# PART_2.net
KiCad netlist of a schematic drawn in Altium Designer
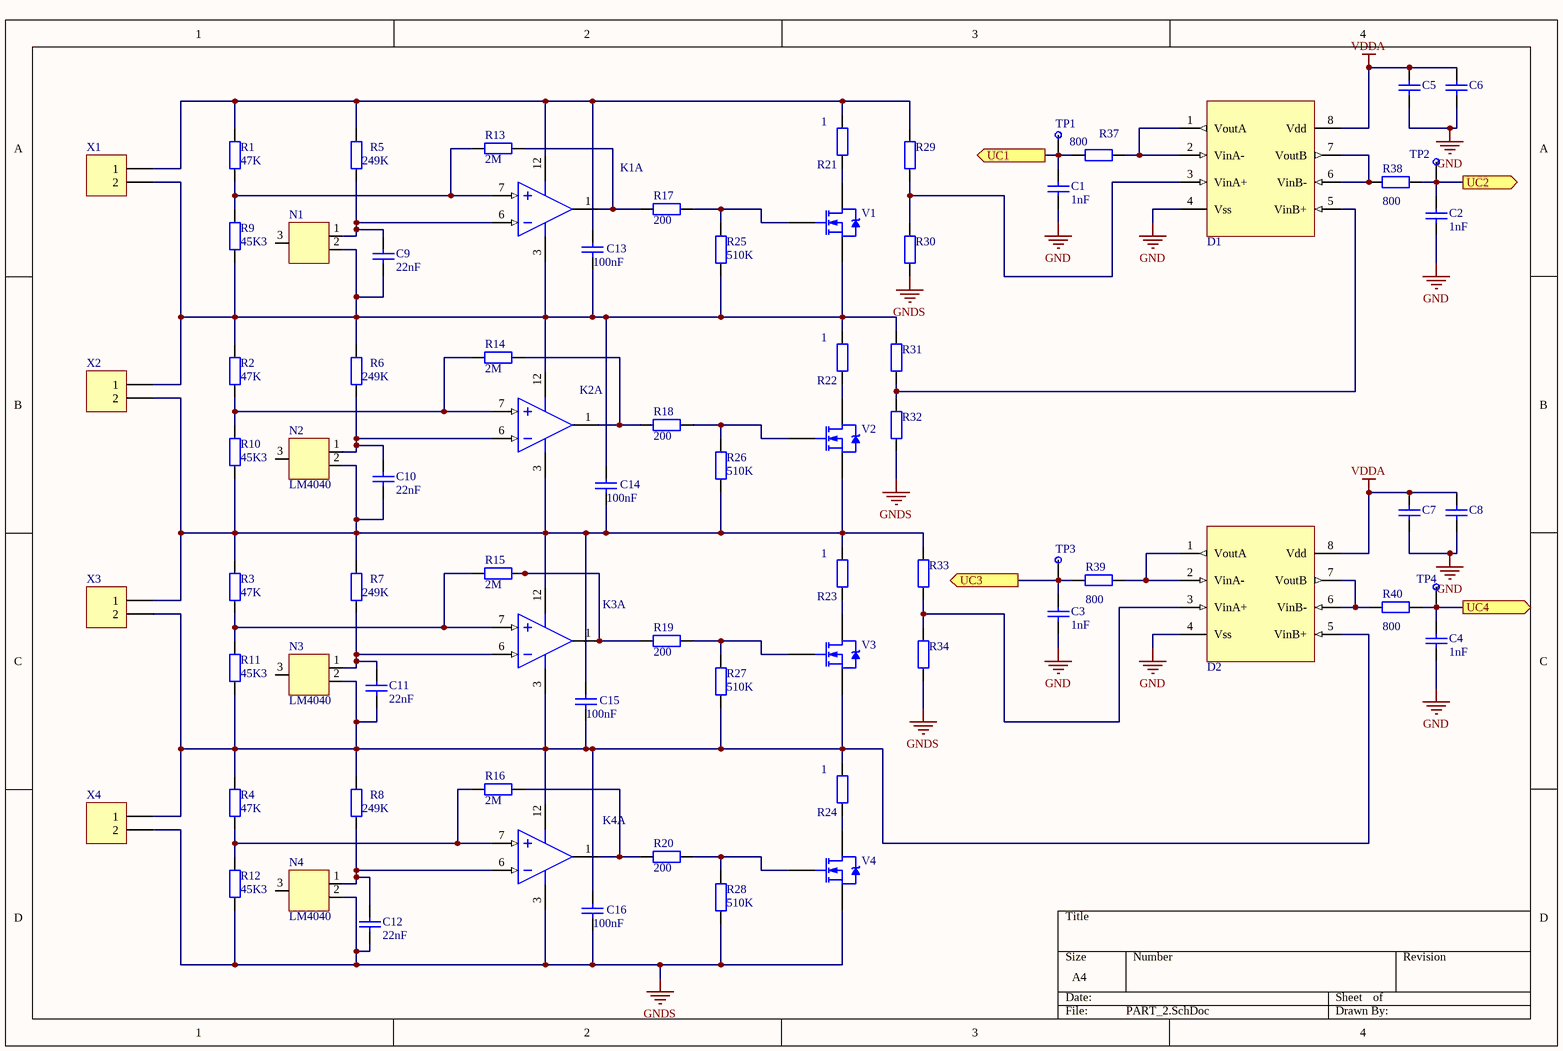
[diagram p0: PART_2.SchDoc]

(export (version "E")
  (design (tool "Eeschema 10.0.6"))
  (components
    (comp (ref "C1")
      (value "1nF")
      (footprint "C0805")
      (description "Capacitor")
      (fields (field (name "Comment") "Cap"))
      (libsource (lib "Miscellaneous Devices") (part "Cap"))
    )
    (comp (ref "C2")
      (value "1nF")
      (footprint "C0805")
      (description "Capacitor")
      (fields (field (name "Comment") "Cap"))
      (libsource (lib "Miscellaneous Devices") (part "Cap"))
    )
    (comp (ref "C3")
      (value "1nF")
      (footprint "C0805")
      (description "Capacitor")
      (fields (field (name "Comment") "Cap"))
      (libsource (lib "Miscellaneous Devices") (part "Cap"))
    )
    (comp (ref "C4")
      (value "1nF")
      (footprint "C0805")
      (description "Capacitor")
      (fields (field (name "Comment") "Cap"))
      (libsource (lib "Miscellaneous Devices") (part "Cap"))
    )
    (comp (ref "C5")
      (value "Cap")
      (footprint "C0805")
      (description "Capacitor")
      (libsource (lib "Miscellaneous Devices") (part "Cap"))
    )
    (comp (ref "C6")
      (value "Cap")
      (footprint "C0805")
      (description "Capacitor")
      (libsource (lib "Miscellaneous Devices") (part "Cap"))
    )
    (comp (ref "C7")
      (value "Cap")
      (footprint "C0805")
      (description "Capacitor")
      (libsource (lib "Miscellaneous Devices") (part "Cap"))
    )
    (comp (ref "C8")
      (value "Cap")
      (footprint "C0805")
      (description "Capacitor")
      (libsource (lib "Miscellaneous Devices") (part "Cap"))
    )
    (comp (ref "C9")
      (value "22nF")
      (footprint "C0805")
      (description "Capacitor")
      (fields (field (name "Comment") "Cap"))
      (libsource (lib "Miscellaneous Devices") (part "Cap"))
    )
    (comp (ref "C10")
      (value "22nF")
      (footprint "C0805")
      (description "Capacitor")
      (fields (field (name "Comment") "Cap"))
      (libsource (lib "Miscellaneous Devices") (part "Cap"))
    )
    (comp (ref "C11")
      (value "22nF")
      (footprint "C0805")
      (description "Capacitor")
      (fields (field (name "Comment") "Cap"))
      (libsource (lib "Miscellaneous Devices") (part "Cap"))
    )
    (comp (ref "C12")
      (value "22nF")
      (footprint "C0805")
      (description "Capacitor")
      (fields (field (name "Comment") "Cap"))
      (libsource (lib "Miscellaneous Devices") (part "Cap"))
    )
    (comp (ref "C13")
      (value "100nF")
      (footprint "C0805")
      (description "Capacitor")
      (fields (field (name "Comment") "Cap"))
      (libsource (lib "Miscellaneous Devices") (part "Cap"))
    )
    (comp (ref "C14")
      (value "100nF")
      (footprint "C0805")
      (description "Capacitor")
      (fields (field (name "Comment") "Cap"))
      (libsource (lib "Miscellaneous Devices") (part "Cap"))
    )
    (comp (ref "C15")
      (value "100nF")
      (footprint "C0805")
      (description "Capacitor")
      (fields (field (name "Comment") "Cap"))
      (libsource (lib "Miscellaneous Devices") (part "Cap"))
    )
    (comp (ref "C16")
      (value "100nF")
      (footprint "C0805")
      (description "Capacitor")
      (fields (field (name "Comment") "Cap"))
      (libsource (lib "Miscellaneous Devices") (part "Cap"))
    )
    (comp (ref "D1")
      (value "~")
      (footprint "MSOP za op.pojacalo")
      (libsource (lib "komponente") (part "Amplifier"))
    )
    (comp (ref "D2")
      (value "~")
      (footprint "MSOP za op.pojacalo")
      (libsource (lib "komponente") (part "Amplifier"))
    )
    (comp (ref "K1")
      (value "TLC3704QJ")
      (footprint "TSSOP5-3")
      (description "Low Power Quad Differential Comparator")
      (libsource (lib "TI Analog Comparator") (part "LP2901D"))
    )
    (comp (ref "K2")
      (value "TLC3704QJ")
      (footprint "TSSOP5-3")
      (description "Low Power Quad Differential Comparator")
      (libsource (lib "TI Analog Comparator") (part "LP2901D"))
    )
    (comp (ref "K3")
      (value "TLC3704QJ")
      (footprint "TSSOP5-3")
      (description "Low Power Quad Differential Comparator")
      (libsource (lib "TI Analog Comparator") (part "LP2901D"))
    )
    (comp (ref "K4")
      (value "TLC3704QJ")
      (footprint "TSSOP5-3")
      (description "Low Power Quad Differential Comparator")
      (libsource (lib "TI Analog Comparator") (part "LP2901D"))
    )
    (comp (ref "N1")
      (value "~")
      (footprint "SOT-23-ref_chip")
      (libsource (lib "komponente") (part "referentni chip"))
    )
    (comp (ref "N2")
      (value "LM4040")
      (footprint "SOT-23-ref_chip")
      (libsource (lib "komponente") (part "referentni chip"))
    )
    (comp (ref "N3")
      (value "LM4040")
      (footprint "SOT-23-ref_chip")
      (libsource (lib "komponente") (part "referentni chip"))
    )
    (comp (ref "N4")
      (value "LM4040")
      (footprint "SOT-23-ref_chip")
      (libsource (lib "komponente") (part "referentni chip"))
    )
    (comp (ref "R1")
      (value "47K")
      (footprint "C0805")
      (description "Resistor")
      (libsource (lib "Miscellaneous Devices") (part "Res2"))
    )
    (comp (ref "R2")
      (value "47K")
      (footprint "C0805")
      (description "Resistor")
      (libsource (lib "Miscellaneous Devices") (part "Res2"))
    )
    (comp (ref "R3")
      (value "47K")
      (footprint "C0805")
      (description "Resistor")
      (libsource (lib "Miscellaneous Devices") (part "Res2"))
    )
    (comp (ref "R4")
      (value "47K")
      (footprint "C0805")
      (description "Resistor")
      (libsource (lib "Miscellaneous Devices") (part "Res2"))
    )
    (comp (ref "R5")
      (value "249K")
      (footprint "C0805")
      (description "Resistor")
      (libsource (lib "Miscellaneous Devices") (part "Res2"))
    )
    (comp (ref "R6")
      (value "249K")
      (footprint "C0805")
      (description "Resistor")
      (libsource (lib "Miscellaneous Devices") (part "Res2"))
    )
    (comp (ref "R7")
      (value "249K")
      (footprint "C0805")
      (description "Resistor")
      (libsource (lib "Miscellaneous Devices") (part "Res2"))
    )
    (comp (ref "R8")
      (value "249K")
      (footprint "C0805")
      (description "Resistor")
      (libsource (lib "Miscellaneous Devices") (part "Res2"))
    )
    (comp (ref "R9")
      (value "45K3")
      (footprint "C0805")
      (description "Resistor")
      (libsource (lib "Miscellaneous Devices") (part "Res2"))
    )
    (comp (ref "R10")
      (value "45K3")
      (footprint "C0805")
      (description "Resistor")
      (libsource (lib "Miscellaneous Devices") (part "Res2"))
    )
    (comp (ref "R11")
      (value "45K3")
      (footprint "C0805")
      (description "Resistor")
      (libsource (lib "Miscellaneous Devices") (part "Res2"))
    )
    (comp (ref "R12")
      (value "45K3")
      (footprint "C0805")
      (description "Resistor")
      (libsource (lib "Miscellaneous Devices") (part "Res2"))
    )
    (comp (ref "R13")
      (value "2M")
      (footprint "C0805")
      (description "Resistor")
      (libsource (lib "") (part "Res2_1"))
    )
    (comp (ref "R14")
      (value "2M")
      (footprint "C0805")
      (description "Resistor")
      (libsource (lib "") (part "Res2_1"))
    )
    (comp (ref "R15")
      (value "2M")
      (footprint "C0805")
      (description "Resistor")
      (libsource (lib "") (part "Res2_1"))
    )
    (comp (ref "R16")
      (value "2M")
      (footprint "C0805")
      (description "Resistor")
      (libsource (lib "") (part "Res2_1"))
    )
    (comp (ref "R17")
      (value "200")
      (footprint "C0805")
      (description "Resistor")
      (libsource (lib "") (part "Res2_1"))
    )
    (comp (ref "R18")
      (value "200")
      (footprint "C0805")
      (description "Resistor")
      (libsource (lib "") (part "Res2_1"))
    )
    (comp (ref "R19")
      (value "200")
      (footprint "C0805")
      (description "Resistor")
      (libsource (lib "") (part "Res2_1"))
    )
    (comp (ref "R20")
      (value "200")
      (footprint "C0805")
      (description "Resistor")
      (libsource (lib "") (part "Res2_1"))
    )
    (comp (ref "R21")
      (value "1")
      (footprint "F za 7W otpornik")
      (description "Resistor")
      (libsource (lib "Miscellaneous Devices") (part "Res2"))
    )
    (comp (ref "R22")
      (value "1")
      (footprint "F za 7W otpornik")
      (description "Resistor")
      (libsource (lib "Miscellaneous Devices") (part "Res2"))
    )
    (comp (ref "R23")
      (value "1")
      (footprint "F za 7W otpornik")
      (description "Resistor")
      (libsource (lib "Miscellaneous Devices") (part "Res2"))
    )
    (comp (ref "R24")
      (value "1")
      (footprint "F za 7W otpornik")
      (description "Resistor")
      (libsource (lib "Miscellaneous Devices") (part "Res2"))
    )
    (comp (ref "R25")
      (value "510K")
      (footprint "C0805")
      (description "Resistor")
      (libsource (lib "Miscellaneous Devices") (part "Res2"))
    )
    (comp (ref "R26")
      (value "510K")
      (footprint "C0805")
      (description "Resistor")
      (libsource (lib "Miscellaneous Devices") (part "Res2"))
    )
    (comp (ref "R27")
      (value "510K")
      (footprint "C0805")
      (description "Resistor")
      (libsource (lib "Miscellaneous Devices") (part "Res2"))
    )
    (comp (ref "R28")
      (value "510K")
      (footprint "C0805")
      (description "Resistor")
      (libsource (lib "Miscellaneous Devices") (part "Res2"))
    )
    (comp (ref "R29")
      (value "~")
      (footprint "C0805")
      (description "Resistor")
      (libsource (lib "Miscellaneous Devices") (part "Res2"))
    )
    (comp (ref "R30")
      (value "~")
      (footprint "C0805")
      (description "Resistor")
      (libsource (lib "Miscellaneous Devices") (part "Res2"))
    )
    (comp (ref "R31")
      (value "~")
      (footprint "C0805")
      (description "Resistor")
      (libsource (lib "Miscellaneous Devices") (part "Res2"))
    )
    (comp (ref "R32")
      (value "~")
      (footprint "C0805")
      (description "Resistor")
      (libsource (lib "Miscellaneous Devices") (part "Res2"))
    )
    (comp (ref "R33")
      (value "~")
      (footprint "C0805")
      (description "Resistor")
      (libsource (lib "Miscellaneous Devices") (part "Res2"))
    )
    (comp (ref "R34")
      (value "~")
      (footprint "C0805")
      (description "Resistor")
      (libsource (lib "Miscellaneous Devices") (part "Res2"))
    )
    (comp (ref "R37")
      (value "800")
      (footprint "C0805")
      (description "Resistor")
      (libsource (lib "") (part "Res2_1"))
    )
    (comp (ref "R38")
      (value "800")
      (footprint "C0805")
      (description "Resistor")
      (libsource (lib "") (part "Res2_2"))
    )
    (comp (ref "R39")
      (value "800")
      (footprint "C0805")
      (description "Resistor")
      (libsource (lib "") (part "Res2_2"))
    )
    (comp (ref "R40")
      (value "800")
      (footprint "C0805")
      (description "Resistor")
      (libsource (lib "") (part "Res2_2"))
    )
    (comp (ref "TP1")
      (value "testpoint")
      (footprint "Test_point")
      (libsource (lib "komponente") (part "testpoint"))
    )
    (comp (ref "TP2")
      (value "testpoint")
      (footprint "Test_point")
      (libsource (lib "komponente") (part "testpoint"))
    )
    (comp (ref "TP3")
      (value "testpoint")
      (footprint "Test_point")
      (libsource (lib "komponente") (part "testpoint"))
    )
    (comp (ref "TP4")
      (value "testpoint")
      (footprint "Test_point")
      (libsource (lib "komponente") (part "testpoint"))
    )
    (comp (ref "V1")
      (value "NMOS-2")
      (footprint "sot23_transistors")
      (description "N-Channel Power MOSFET")
      (libsource (lib "Miscellaneous Devices") (part "NMOS-2"))
    )
    (comp (ref "V2")
      (value "NMOS-2")
      (footprint "sot23_transistors")
      (description "N-Channel Power MOSFET")
      (libsource (lib "Miscellaneous Devices") (part "NMOS-2"))
    )
    (comp (ref "V3")
      (value "NMOS-2")
      (footprint "sot23_transistors")
      (description "N-Channel Power MOSFET")
      (libsource (lib "Miscellaneous Devices") (part "NMOS-2"))
    )
    (comp (ref "V4")
      (value "NMOS-2")
      (footprint "sot23_transistors")
      (description "N-Channel Power MOSFET")
      (libsource (lib "Miscellaneous Devices") (part "NMOS-2"))
    )
    (comp (ref "X1")
      (value "Header 2")
      (footprint "F Header 1x2")
      (description "Header, 2-Pin")
      (libsource (lib "Miscellaneous Connectors") (part "Header 2"))
    )
    (comp (ref "X2")
      (value "Header 2")
      (footprint "F Header 1x2")
      (description "Header, 2-Pin")
      (libsource (lib "Miscellaneous Connectors") (part "Header 2"))
    )
    (comp (ref "X3")
      (value "Header 2")
      (footprint "F Header 1x2")
      (description "Header, 2-Pin")
      (libsource (lib "Miscellaneous Connectors") (part "Header 2"))
    )
    (comp (ref "X4")
      (value "Header 2")
      (footprint "F Header 1x2")
      (description "Header, 2-Pin")
      (libsource (lib "Miscellaneous Connectors") (part "Header 2"))
    )
  )
  (nets
    (net (code "1") (name "/UC1") (class "Default")
      (node (ref "C1") (pin "2") (pinfunction "2_2") (pintype "passive"))
      (node (ref "R37") (pin "2") (pinfunction "2_2") (pintype "passive"))
      (node (ref "TP1") (pin "1") (pinfunction "1_1") (pintype "passive"))
    )
    (net (code "2") (name "/UC2") (class "Default")
      (node (ref "C2") (pin "2") (pinfunction "2_2") (pintype "passive"))
      (node (ref "R38") (pin "2") (pinfunction "2_2") (pintype "passive"))
      (node (ref "TP2") (pin "1") (pinfunction "1_1") (pintype "passive"))
    )
    (net (code "3") (name "/UC3") (class "Default")
      (node (ref "C3") (pin "2") (pinfunction "2_2") (pintype "passive"))
      (node (ref "R39") (pin "1") (pinfunction "1_1") (pintype "passive"))
      (node (ref "TP3") (pin "1") (pinfunction "1_1") (pintype "passive"))
    )
    (net (code "4") (name "/UC4") (class "Default")
      (node (ref "C4") (pin "2") (pinfunction "2_2") (pintype "passive"))
      (node (ref "R40") (pin "2") (pinfunction "2_2") (pintype "passive"))
      (node (ref "TP4") (pin "1") (pinfunction "1_1") (pintype "passive"))
    )
    (net (code "5") (name "GND") (class "Default")
      (node (ref "C1") (pin "1") (pinfunction "1_1") (pintype "passive"))
      (node (ref "C2") (pin "1") (pinfunction "1_1") (pintype "passive"))
      (node (ref "C3") (pin "1") (pinfunction "1_1") (pintype "passive"))
      (node (ref "C4") (pin "1") (pinfunction "1_1") (pintype "passive"))
      (node (ref "C5") (pin "1") (pinfunction "1_1") (pintype "passive"))
      (node (ref "C6") (pin "1") (pinfunction "1_1") (pintype "passive"))
      (node (ref "C7") (pin "1") (pinfunction "1_1") (pintype "passive"))
      (node (ref "C8") (pin "1") (pinfunction "1_1") (pintype "passive"))
      (node (ref "D1") (pin "4") (pinfunction "Vss_4") (pintype "power_in"))
      (node (ref "D2") (pin "4") (pinfunction "Vss_4") (pintype "power_in"))
    )
    (net (code "6") (name "GNDS") (class "Default")
      (node (ref "C12") (pin "1") (pinfunction "1_1") (pintype "passive"))
      (node (ref "C16") (pin "2") (pinfunction "2_2") (pintype "passive"))
      (node (ref "K4") (pin "3") (pinfunction "V+_3") (pintype "passive"))
      (node (ref "N4") (pin "2") (pinfunction "2_2") (pintype "passive"))
      (node (ref "R12") (pin "1") (pinfunction "1_1") (pintype "passive"))
      (node (ref "R28") (pin "1") (pinfunction "1_1") (pintype "passive"))
      (node (ref "R30") (pin "1") (pinfunction "1_1") (pintype "passive"))
      (node (ref "R32") (pin "1") (pinfunction "1_1") (pintype "passive"))
      (node (ref "R34") (pin "1") (pinfunction "1_1") (pintype "passive"))
      (node (ref "V4") (pin "3") (pinfunction "S_3") (pintype "passive"))
      (node (ref "X4") (pin "2") (pinfunction "2_2") (pintype "passive"))
    )
    (net (code "7") (name "Net-(D1-VinA+)") (class "Default")
      (node (ref "D1") (pin "3") (pinfunction "VinA+_3") (pintype "input"))
      (node (ref "R29") (pin "1") (pinfunction "1_1") (pintype "passive"))
      (node (ref "R30") (pin "2") (pinfunction "2_2") (pintype "passive"))
    )
    (net (code "8") (name "Net-(D1-VinA-)") (class "Default")
      (node (ref "D1") (pin "1") (pinfunction "VoutA_1") (pintype "output"))
      (node (ref "D1") (pin "2") (pinfunction "VinA-_2") (pintype "input"))
      (node (ref "R37") (pin "1") (pinfunction "1_1") (pintype "passive"))
    )
    (net (code "9") (name "Net-(D1-VinB+)") (class "Default")
      (node (ref "D1") (pin "5") (pinfunction "VinB+_5") (pintype "input"))
      (node (ref "R31") (pin "1") (pinfunction "1_1") (pintype "passive"))
      (node (ref "R32") (pin "2") (pinfunction "2_2") (pintype "passive"))
    )
    (net (code "10") (name "Net-(D1-VinB-)") (class "Default")
      (node (ref "D1") (pin "6") (pinfunction "VinB-_6") (pintype "input"))
      (node (ref "D1") (pin "7") (pinfunction "VoutB_7") (pintype "output"))
      (node (ref "R38") (pin "1") (pinfunction "1_1") (pintype "passive"))
    )
    (net (code "11") (name "Net-(D2-VinA+)") (class "Default")
      (node (ref "D2") (pin "3") (pinfunction "VinA+_3") (pintype "input"))
      (node (ref "R33") (pin "1") (pinfunction "1_1") (pintype "passive"))
      (node (ref "R34") (pin "2") (pinfunction "2_2") (pintype "passive"))
    )
    (net (code "12") (name "Net-(D2-VinA-)") (class "Default")
      (node (ref "D2") (pin "1") (pinfunction "VoutA_1") (pintype "output"))
      (node (ref "D2") (pin "2") (pinfunction "VinA-_2") (pintype "input"))
      (node (ref "R39") (pin "2") (pinfunction "2_2") (pintype "passive"))
    )
    (net (code "13") (name "Net-(D2-VinB+)") (class "Default")
      (node (ref "C11") (pin "1") (pinfunction "1_1") (pintype "passive"))
      (node (ref "C15") (pin "2") (pinfunction "2_2") (pintype "passive"))
      (node (ref "C16") (pin "1") (pinfunction "1_1") (pintype "passive"))
      (node (ref "D2") (pin "5") (pinfunction "VinB+_5") (pintype "input"))
      (node (ref "K3") (pin "3") (pinfunction "V+_3") (pintype "passive"))
      (node (ref "K4") (pin "12") (pinfunction "V-_12") (pintype "passive"))
      (node (ref "N3") (pin "2") (pinfunction "2_2") (pintype "passive"))
      (node (ref "R11") (pin "1") (pinfunction "1_1") (pintype "passive"))
      (node (ref "R24") (pin "2") (pinfunction "2_2") (pintype "passive"))
      (node (ref "R27") (pin "1") (pinfunction "1_1") (pintype "passive"))
      (node (ref "R4") (pin "2") (pinfunction "2_2") (pintype "passive"))
      (node (ref "R8") (pin "2") (pinfunction "2_2") (pintype "passive"))
      (node (ref "V3") (pin "3") (pinfunction "S_3") (pintype "passive"))
      (node (ref "X3") (pin "2") (pinfunction "2_2") (pintype "passive"))
      (node (ref "X4") (pin "1") (pinfunction "1_1") (pintype "passive"))
    )
    (net (code "14") (name "Net-(D2-VinB-)") (class "Default")
      (node (ref "D2") (pin "6") (pinfunction "VinB-_6") (pintype "input"))
      (node (ref "D2") (pin "7") (pinfunction "VoutB_7") (pintype "output"))
      (node (ref "R40") (pin "1") (pinfunction "1_1") (pintype "passive"))
    )
    (net (code "15") (name "Net-(K1A-IN+)") (class "Default")
      (node (ref "K1") (pin "7") (pinfunction "IN+_7") (pintype "input"))
      (node (ref "R1") (pin "1") (pinfunction "1_1") (pintype "passive"))
      (node (ref "R13") (pin "2") (pinfunction "2_2") (pintype "passive"))
      (node (ref "R9") (pin "2") (pinfunction "2_2") (pintype "passive"))
    )
    (net (code "16") (name "Net-(K1A-IN-)") (class "Default")
      (node (ref "C9") (pin "2") (pinfunction "2_2") (pintype "passive"))
      (node (ref "K1") (pin "6") (pinfunction "IN-_6") (pintype "input"))
      (node (ref "N1") (pin "1") (pinfunction "1_1") (pintype "bidirectional"))
      (node (ref "R5") (pin "1") (pinfunction "1_1") (pintype "passive"))
    )
    (net (code "17") (name "Net-(K1A-OUT)") (class "Default")
      (node (ref "K1") (pin "1") (pinfunction "OUT_1") (pintype "open_collector"))
      (node (ref "R13") (pin "1") (pinfunction "1_1") (pintype "passive"))
      (node (ref "R17") (pin "2") (pinfunction "2_2") (pintype "passive"))
    )
    (net (code "18") (name "Net-(K1A-V+)") (class "Default")
      (node (ref "C13") (pin "2") (pinfunction "2_2") (pintype "passive"))
      (node (ref "C14") (pin "1") (pinfunction "1_1") (pintype "passive"))
      (node (ref "C9") (pin "1") (pinfunction "1_1") (pintype "passive"))
      (node (ref "K1") (pin "3") (pinfunction "V+_3") (pintype "passive"))
      (node (ref "K2") (pin "12") (pinfunction "V-_12") (pintype "passive"))
      (node (ref "N1") (pin "2") (pinfunction "2_2") (pintype "passive"))
      (node (ref "R2") (pin "2") (pinfunction "2_2") (pintype "passive"))
      (node (ref "R22") (pin "2") (pinfunction "2_2") (pintype "passive"))
      (node (ref "R25") (pin "1") (pinfunction "1_1") (pintype "passive"))
      (node (ref "R31") (pin "2") (pinfunction "2_2") (pintype "passive"))
      (node (ref "R6") (pin "2") (pinfunction "2_2") (pintype "passive"))
      (node (ref "R9") (pin "1") (pinfunction "1_1") (pintype "passive"))
      (node (ref "V1") (pin "3") (pinfunction "S_3") (pintype "passive"))
      (node (ref "X1") (pin "2") (pinfunction "2_2") (pintype "passive"))
      (node (ref "X2") (pin "1") (pinfunction "1_1") (pintype "passive"))
    )
    (net (code "19") (name "Net-(K1A-V-)") (class "Default")
      (node (ref "C13") (pin "1") (pinfunction "1_1") (pintype "passive"))
      (node (ref "K1") (pin "12") (pinfunction "V-_12") (pintype "passive"))
      (node (ref "R1") (pin "2") (pinfunction "2_2") (pintype "passive"))
      (node (ref "R21") (pin "2") (pinfunction "2_2") (pintype "passive"))
      (node (ref "R29") (pin "2") (pinfunction "2_2") (pintype "passive"))
      (node (ref "R5") (pin "2") (pinfunction "2_2") (pintype "passive"))
      (node (ref "X1") (pin "1") (pinfunction "1_1") (pintype "passive"))
    )
    (net (code "20") (name "Net-(K2A-IN+)") (class "Default")
      (node (ref "K2") (pin "7") (pinfunction "IN+_7") (pintype "input"))
      (node (ref "R10") (pin "2") (pinfunction "2_2") (pintype "passive"))
      (node (ref "R14") (pin "2") (pinfunction "2_2") (pintype "passive"))
      (node (ref "R2") (pin "1") (pinfunction "1_1") (pintype "passive"))
    )
    (net (code "21") (name "Net-(K2A-IN-)") (class "Default")
      (node (ref "C10") (pin "2") (pinfunction "2_2") (pintype "passive"))
      (node (ref "K2") (pin "6") (pinfunction "IN-_6") (pintype "input"))
      (node (ref "N2") (pin "1") (pinfunction "1_1") (pintype "bidirectional"))
      (node (ref "R6") (pin "1") (pinfunction "1_1") (pintype "passive"))
    )
    (net (code "22") (name "Net-(K2A-OUT)") (class "Default")
      (node (ref "K2") (pin "1") (pinfunction "OUT_1") (pintype "open_collector"))
      (node (ref "R14") (pin "1") (pinfunction "1_1") (pintype "passive"))
      (node (ref "R18") (pin "2") (pinfunction "2_2") (pintype "passive"))
    )
    (net (code "23") (name "Net-(K2A-V+)") (class "Default")
      (node (ref "C10") (pin "1") (pinfunction "1_1") (pintype "passive"))
      (node (ref "C14") (pin "2") (pinfunction "2_2") (pintype "passive"))
      (node (ref "C15") (pin "1") (pinfunction "1_1") (pintype "passive"))
      (node (ref "K2") (pin "3") (pinfunction "V+_3") (pintype "passive"))
      (node (ref "K3") (pin "12") (pinfunction "V-_12") (pintype "passive"))
      (node (ref "N2") (pin "2") (pinfunction "2_2") (pintype "passive"))
      (node (ref "R10") (pin "1") (pinfunction "1_1") (pintype "passive"))
      (node (ref "R23") (pin "2") (pinfunction "2_2") (pintype "passive"))
      (node (ref "R26") (pin "1") (pinfunction "1_1") (pintype "passive"))
      (node (ref "R3") (pin "2") (pinfunction "2_2") (pintype "passive"))
      (node (ref "R33") (pin "2") (pinfunction "2_2") (pintype "passive"))
      (node (ref "R7") (pin "2") (pinfunction "2_2") (pintype "passive"))
      (node (ref "V2") (pin "3") (pinfunction "S_3") (pintype "passive"))
      (node (ref "X2") (pin "2") (pinfunction "2_2") (pintype "passive"))
      (node (ref "X3") (pin "1") (pinfunction "1_1") (pintype "passive"))
    )
    (net (code "24") (name "Net-(K3A-IN+)") (class "Default")
      (node (ref "K3") (pin "7") (pinfunction "IN+_7") (pintype "input"))
      (node (ref "R11") (pin "2") (pinfunction "2_2") (pintype "passive"))
      (node (ref "R15") (pin "2") (pinfunction "2_2") (pintype "passive"))
      (node (ref "R3") (pin "1") (pinfunction "1_1") (pintype "passive"))
    )
    (net (code "25") (name "Net-(K3A-IN-)") (class "Default")
      (node (ref "C11") (pin "2") (pinfunction "2_2") (pintype "passive"))
      (node (ref "K3") (pin "6") (pinfunction "IN-_6") (pintype "input"))
      (node (ref "N3") (pin "1") (pinfunction "1_1") (pintype "bidirectional"))
      (node (ref "R7") (pin "1") (pinfunction "1_1") (pintype "passive"))
    )
    (net (code "26") (name "Net-(K3A-OUT)") (class "Default")
      (node (ref "K3") (pin "1") (pinfunction "OUT_1") (pintype "open_collector"))
      (node (ref "R15") (pin "1") (pinfunction "1_1") (pintype "passive"))
      (node (ref "R19") (pin "2") (pinfunction "2_2") (pintype "passive"))
    )
    (net (code "27") (name "Net-(K4A-IN+)") (class "Default")
      (node (ref "K4") (pin "7") (pinfunction "IN+_7") (pintype "input"))
      (node (ref "R12") (pin "2") (pinfunction "2_2") (pintype "passive"))
      (node (ref "R16") (pin "2") (pinfunction "2_2") (pintype "passive"))
      (node (ref "R4") (pin "1") (pinfunction "1_1") (pintype "passive"))
    )
    (net (code "28") (name "Net-(K4A-IN-)") (class "Default")
      (node (ref "C12") (pin "2") (pinfunction "2_2") (pintype "passive"))
      (node (ref "K4") (pin "6") (pinfunction "IN-_6") (pintype "input"))
      (node (ref "N4") (pin "1") (pinfunction "1_1") (pintype "bidirectional"))
      (node (ref "R8") (pin "1") (pinfunction "1_1") (pintype "passive"))
    )
    (net (code "29") (name "Net-(K4A-OUT)") (class "Default")
      (node (ref "K4") (pin "1") (pinfunction "OUT_1") (pintype "open_collector"))
      (node (ref "R16") (pin "1") (pinfunction "1_1") (pintype "passive"))
      (node (ref "R20") (pin "2") (pinfunction "2_2") (pintype "passive"))
    )
    (net (code "30") (name "Net-(V1-D)") (class "Default")
      (node (ref "R21") (pin "1") (pinfunction "1_1") (pintype "passive"))
      (node (ref "V1") (pin "2") (pinfunction "D_2") (pintype "passive"))
    )
    (net (code "31") (name "Net-(V1-G)") (class "Default")
      (node (ref "R17") (pin "1") (pinfunction "1_1") (pintype "passive"))
      (node (ref "R25") (pin "2") (pinfunction "2_2") (pintype "passive"))
      (node (ref "V1") (pin "1") (pinfunction "G_1") (pintype "passive"))
    )
    (net (code "32") (name "Net-(V2-D)") (class "Default")
      (node (ref "R22") (pin "1") (pinfunction "1_1") (pintype "passive"))
      (node (ref "V2") (pin "2") (pinfunction "D_2") (pintype "passive"))
    )
    (net (code "33") (name "Net-(V2-G)") (class "Default")
      (node (ref "R18") (pin "1") (pinfunction "1_1") (pintype "passive"))
      (node (ref "R26") (pin "2") (pinfunction "2_2") (pintype "passive"))
      (node (ref "V2") (pin "1") (pinfunction "G_1") (pintype "passive"))
    )
    (net (code "34") (name "Net-(V3-D)") (class "Default")
      (node (ref "R23") (pin "1") (pinfunction "1_1") (pintype "passive"))
      (node (ref "V3") (pin "2") (pinfunction "D_2") (pintype "passive"))
    )
    (net (code "35") (name "Net-(V3-G)") (class "Default")
      (node (ref "R19") (pin "1") (pinfunction "1_1") (pintype "passive"))
      (node (ref "R27") (pin "2") (pinfunction "2_2") (pintype "passive"))
      (node (ref "V3") (pin "1") (pinfunction "G_1") (pintype "passive"))
    )
    (net (code "36") (name "Net-(V4-D)") (class "Default")
      (node (ref "R24") (pin "1") (pinfunction "1_1") (pintype "passive"))
      (node (ref "V4") (pin "2") (pinfunction "D_2") (pintype "passive"))
    )
    (net (code "37") (name "Net-(V4-G)") (class "Default")
      (node (ref "R20") (pin "1") (pinfunction "1_1") (pintype "passive"))
      (node (ref "R28") (pin "2") (pinfunction "2_2") (pintype "passive"))
      (node (ref "V4") (pin "1") (pinfunction "G_1") (pintype "passive"))
    )
    (net (code "38") (name "VDDA") (class "Default")
      (node (ref "C5") (pin "2") (pinfunction "2_2") (pintype "passive"))
      (node (ref "C6") (pin "2") (pinfunction "2_2") (pintype "passive"))
      (node (ref "C7") (pin "2") (pinfunction "2_2") (pintype "passive"))
      (node (ref "C8") (pin "2") (pinfunction "2_2") (pintype "passive"))
      (node (ref "D1") (pin "8") (pinfunction "Vdd_8") (pintype "power_in"))
      (node (ref "D2") (pin "8") (pinfunction "Vdd_8") (pintype "power_in"))
    )
    (net (code "39") (name "unconnected-(N1-Pad3)") (class "Default")
      (node (ref "N1") (pin "3") (pinfunction "3_3") (pintype "passive"))
    )
    (net (code "40") (name "unconnected-(N2-Pad3)") (class "Default")
      (node (ref "N2") (pin "3") (pinfunction "3_3") (pintype "passive"))
    )
    (net (code "41") (name "unconnected-(N3-Pad3)") (class "Default")
      (node (ref "N3") (pin "3") (pinfunction "3_3") (pintype "passive"))
    )
    (net (code "42") (name "unconnected-(N4-Pad3)") (class "Default")
      (node (ref "N4") (pin "3") (pinfunction "3_3") (pintype "passive"))
    )
    (net (code "43") (name "unconnected-(V1-S-Pad3)") (class "Default")
      (node (ref "V1") (pin "3") (pinfunction "S_3") (pintype "passive"))
    )
    (net (code "44") (name "unconnected-(V1-S-Pad3)_1") (class "Default")
      (node (ref "V1") (pin "3") (pinfunction "S_3") (pintype "passive"))
    )
    (net (code "45") (name "unconnected-(V2-S-Pad3)") (class "Default")
      (node (ref "V2") (pin "3") (pinfunction "S_3") (pintype "passive"))
    )
    (net (code "46") (name "unconnected-(V2-S-Pad3)_1") (class "Default")
      (node (ref "V2") (pin "3") (pinfunction "S_3") (pintype "passive"))
    )
    (net (code "47") (name "unconnected-(V3-S-Pad3)") (class "Default")
      (node (ref "V3") (pin "3") (pinfunction "S_3") (pintype "passive"))
    )
    (net (code "48") (name "unconnected-(V3-S-Pad3)_1") (class "Default")
      (node (ref "V3") (pin "3") (pinfunction "S_3") (pintype "passive"))
    )
    (net (code "49") (name "unconnected-(V4-S-Pad3)") (class "Default")
      (node (ref "V4") (pin "3") (pinfunction "S_3") (pintype "passive"))
    )
    (net (code "50") (name "unconnected-(V4-S-Pad3)_1") (class "Default")
      (node (ref "V4") (pin "3") (pinfunction "S_3") (pintype "passive"))
    )
  )
)
